# -1V_DIST.net
KiCad netlist of a schematic drawn in Altium Designer
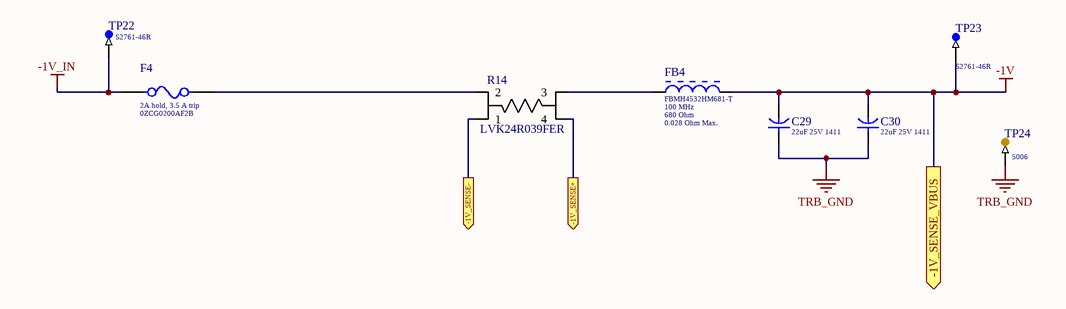
[diagram p0: -1V_DIST.SchDoc]

(export (version "E")
  (design (tool "Eeschema 10.0.6"))
  (components
    (comp (ref "C29")
      (value "Cap_Kemet_T521B226M025ATE100_22uF")
      (footprint "Cap_Kemet_T521B226M025ATE100_22uF")
      (description "Tantalum Capacitors - Polymer SMD 25V 22uF 1311 20% ESR=100mOhms")
      (fields (field (name "CAPACITANCE") "22uF 25V 1411"))
      (libsource (lib "Cap_Kemet_T521B226M025ATE100_22uF") (part "Cap_Kemet_T521B226M025ATE100_22uF"))
    )
    (comp (ref "C30")
      (value "Cap_Kemet_T521B226M025ATE100_22uF")
      (footprint "Cap_Kemet_T521B226M025ATE100_22uF")
      (description "Tantalum Capacitors - Polymer SMD 25V 22uF 1311 20% ESR=100mOhms")
      (fields (field (name "CAPACITANCE") "22uF 25V 1411"))
      (libsource (lib "Cap_Kemet_T521B226M025ATE100_22uF") (part "Cap_Kemet_T521B226M025ATE100_22uF"))
    )
    (comp (ref "F4")
      (value "2A hold, 3.5 A trip")
      (footprint "Bel_0ZCG_MFG")
      (description "2A hold, 3.5A trip")
      (fields (field (name "SERIES") "0ZCG0200AF2B"))
      (libsource (lib "Fuse_Bel_0ZCG0200AF2B_rst_smd") (part "0ZCG0200AF2B"))
    )
    (comp (ref "FB4")
      (value "FBMH4532HM681-T")
      (footprint "TAYO-FBMH4532-2_V")
      (fields
        (field (name "PARTNUMBER") "FBMH4532HM681-T")
        (field (name "MANUFACTURER") "Taiyo Yuden")
        (field (name "MEASURING FREQUENCY") "100 MHz")
        (field (name "NOMINAL IMPEDANCE") "680 Ohm")
        (field (name "DC RESISTANCE") "0.028 Ohm Max.")
      )
      (libsource (lib "Taiyo_Yuden_FBMH4532HM681") (part "FBMH4532HM681-T"))
    )
    (comp (ref "R14")
      (value "LVK24R039FER")
      (footprint "OH_LVK24_OHM")
      (description "RES 0.039 OHM 1% 1W 2412")
      (fields (field (name "COPYRIGHT") "Copyright (C) 2018 Accelerated Designs. All rights reserved"))
      (libsource (lib "Shunt_Res_Ohmite_LVK24R039FER") (part "LVK24R039FER"))
    )
    (comp (ref "TP22")
      (value "TP_Harwin_S2761_46R")
      (footprint "TP_Harwin_S2761_46R")
      (description "Circuit Board Hardware - PCB SMT Mini Test Terminal, Reel")
      (fields (field (name "SERIES") "S2761-46R"))
      (libsource (lib "TP_Harwin_S2761_46R") (part "TP_Harwin_S2761_46R"))
    )
    (comp (ref "TP23")
      (value "TP_Harwin_S2761_46R")
      (footprint "TP_Harwin_S2761_46R")
      (description "Circuit Board Hardware - PCB SMT Mini Test Terminal, Reel")
      (fields (field (name "SERIES") "S2761-46R"))
      (libsource (lib "TP_Harwin_S2761_46R") (part "TP_Harwin_S2761_46R"))
    )
    (comp (ref "TP24")
      (value "TP_Keystone_Electronics_5006")
      (footprint "TP_Keystone_Electronics_5006")
      (description "Circuit Board Hardware - PCB TEST POINT BLK .063")
      (fields (field (name "SERIES") "5006"))
      (libsource (lib "TP_Keystone_Electronics_5006") (part "TP_Keystone_Electronics_5006"))
    )
  )
  (nets
    (net (code "1") (name "-1V") (class "Default")
      (node (ref "C29") (pin "2") (pinfunction "2_2") (pintype "passive"))
      (node (ref "C30") (pin "2") (pinfunction "2_2") (pintype "passive"))
      (node (ref "FB4") (pin "2") (pinfunction "2_2") (pintype "passive"))
      (node (ref "TP23") (pin "1") (pinfunction "1_1") (pintype "input"))
    )
    (net (code "2") (name "-1V_IN") (class "Default")
      (node (ref "F4") (pin "1") (pinfunction "1_1") (pintype "passive"))
      (node (ref "TP22") (pin "1") (pinfunction "1_1") (pintype "input"))
    )
    (net (code "3") (name "/-1V_SENSE+") (class "Default")
      (node (ref "R14") (pin "4") (pinfunction "4_4") (pintype "passive"))
    )
    (net (code "4") (name "/-1V_SENSE-") (class "Default")
      (node (ref "R14") (pin "1") (pinfunction "1_1") (pintype "passive"))
    )
    (net (code "5") (name "Net-(F4-Pad2)") (class "Default")
      (node (ref "F4") (pin "2") (pinfunction "2_2") (pintype "passive"))
      (node (ref "R14") (pin "2") (pinfunction "2_2") (pintype "passive"))
    )
    (net (code "6") (name "Net-(FB4-Pad1)") (class "Default")
      (node (ref "FB4") (pin "1") (pinfunction "1_1") (pintype "passive"))
      (node (ref "R14") (pin "3") (pinfunction "3_3") (pintype "passive"))
    )
    (net (code "7") (name "TRB_GND") (class "Default")
      (node (ref "C29") (pin "1") (pinfunction "1_1") (pintype "passive"))
      (node (ref "C30") (pin "1") (pinfunction "1_1") (pintype "passive"))
      (node (ref "TP24") (pin "1") (pinfunction "1_1") (pintype "input"))
    )
  )
)
